# MCU025B_AltRouting_Misc.net
KiCad netlist of a schematic drawn in Altium Designer
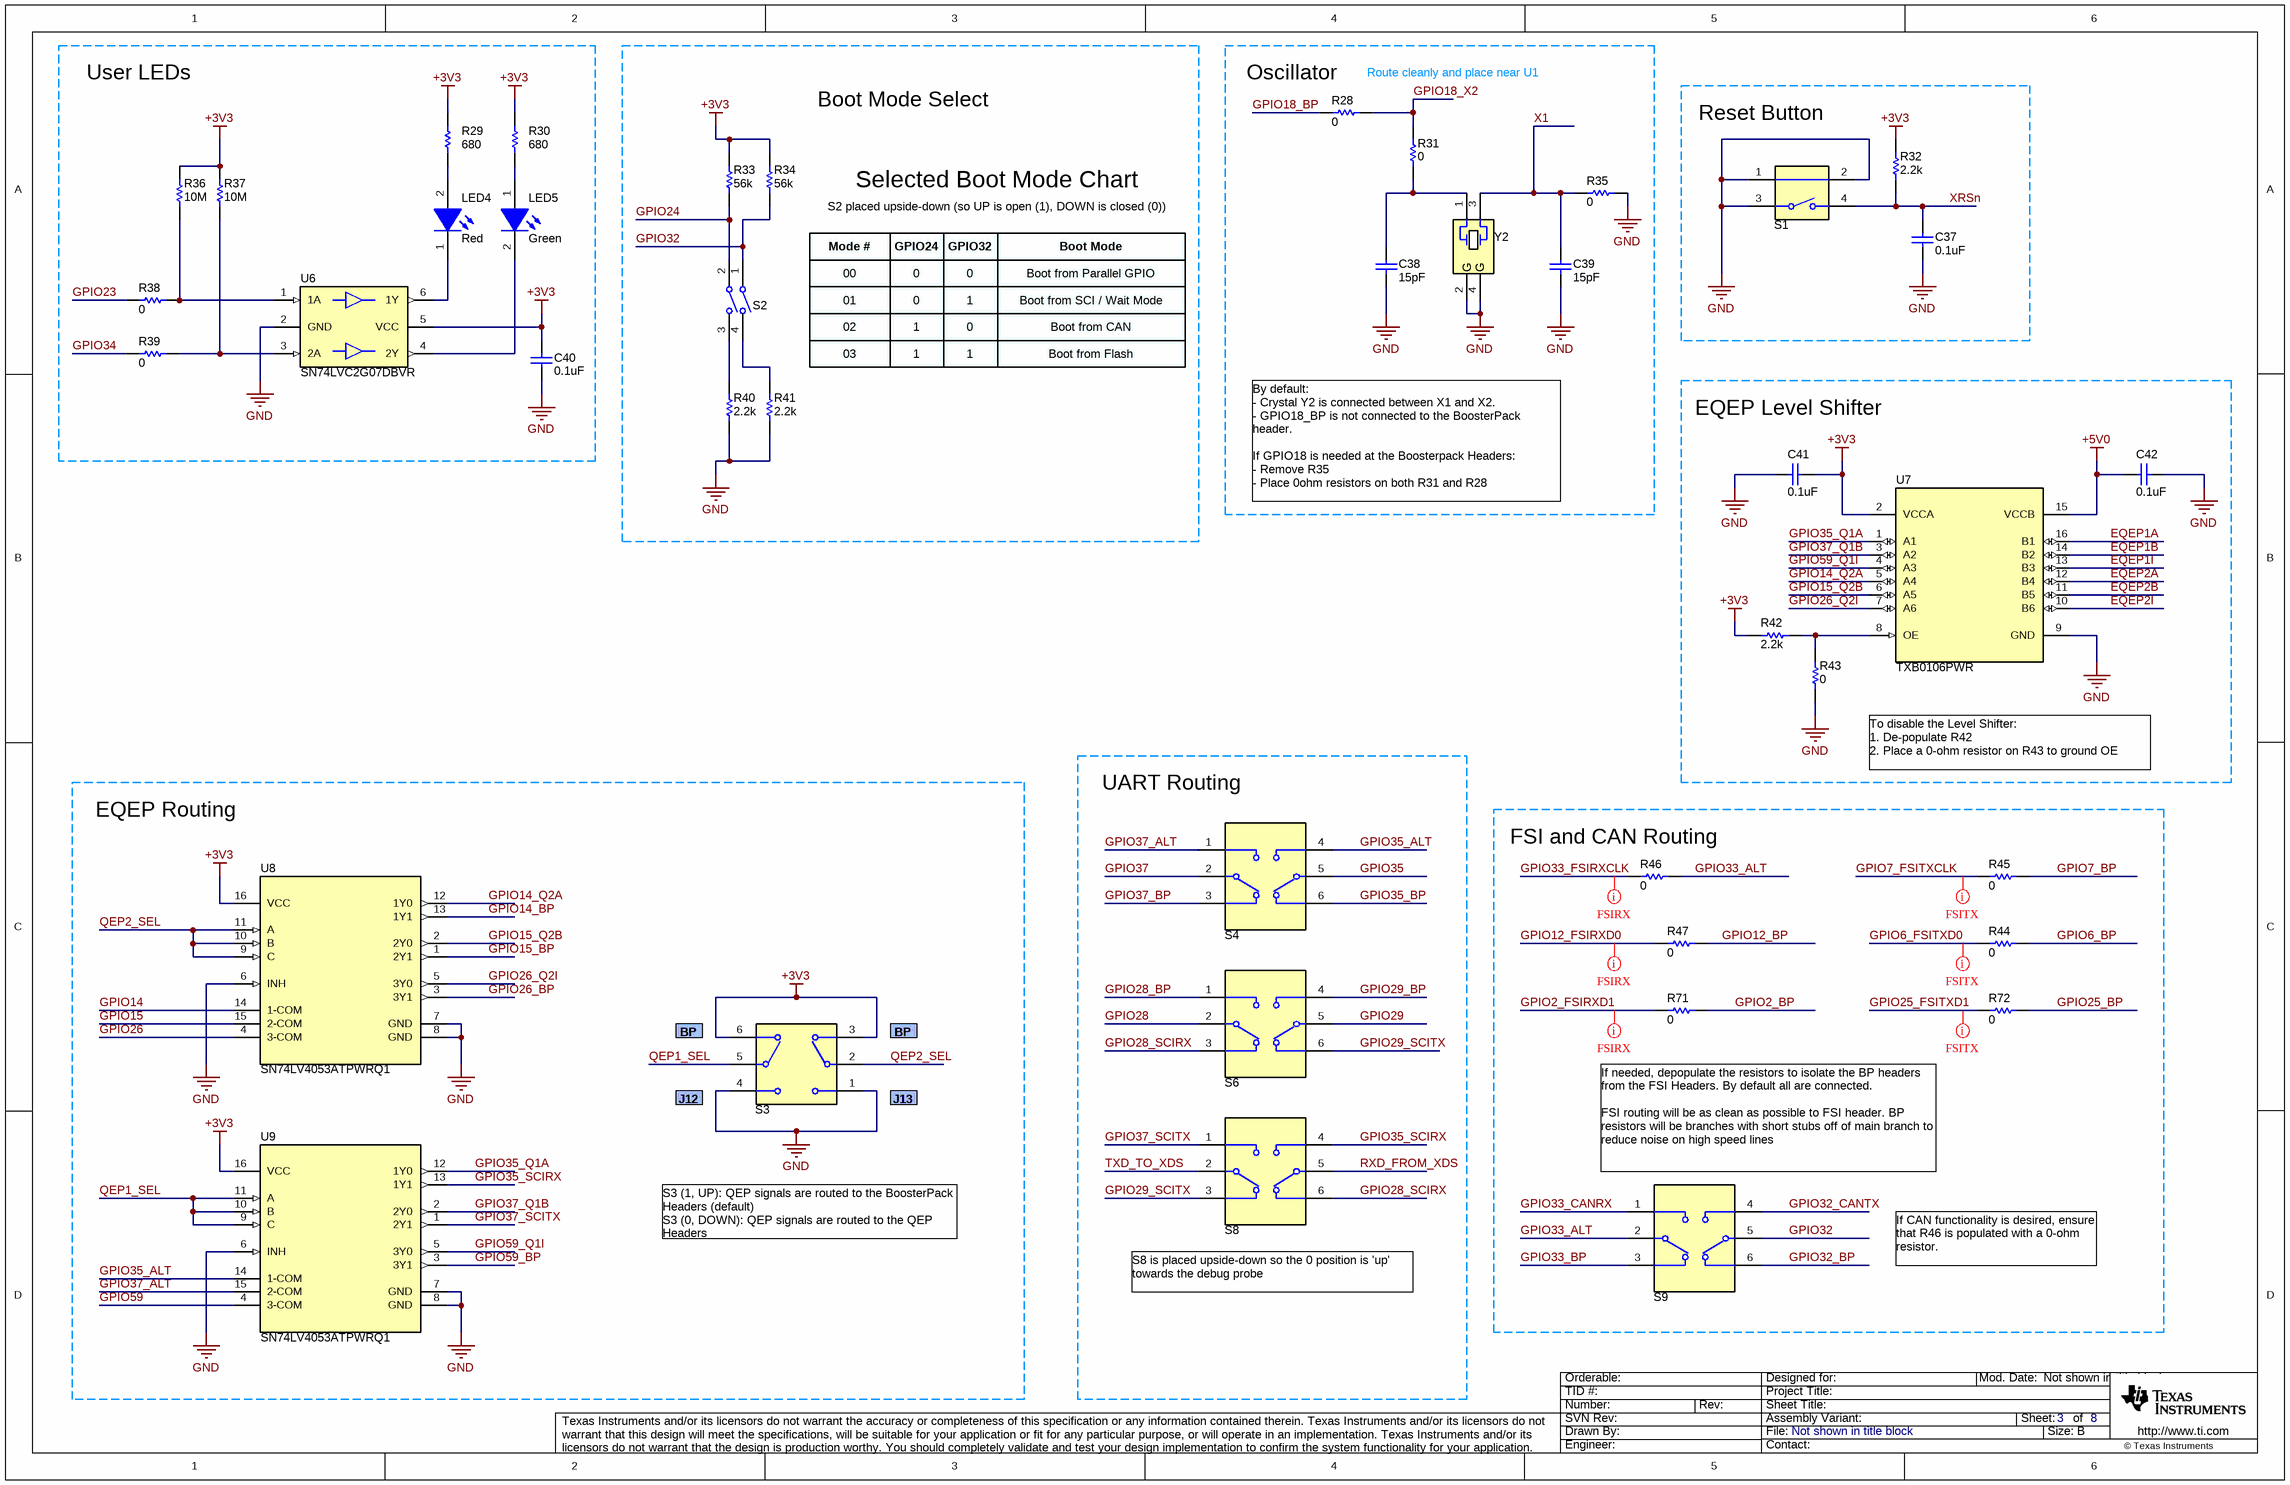
[diagram p0: MCU025B_AltRouting_Misc.SchDoc]

(export (version "E")
  (design (tool "Eeschema 10.0.6"))
  (components
    (comp (ref "C37")
      (value "GRM155R71A104KA01D")
      (footprint "0402")
      (description "CAP, CERM, 0.1 uF, 10 V, +/- 10%, X7R, 0402")
      (fields
        (field (name "VALUEDISPLAYED") "0.1uF")
        (field (name "MANUFACTURER") "MuRata")
        (field (name "PUBLISHER") "Texas Instruments")
      )
      (libsource (lib "Altium Vault - TI") (part "Capacitor"))
    )
    (comp (ref "C38")
      (value "GRM1555C1H150JA01D")
      (footprint "0402")
      (description "CAP, CERM, 15 pF, 50 V, +/- 5%, C0G/NP0, 0402")
      (fields
        (field (name "VALUEDISPLAYED") "15pF")
        (field (name "MANUFACTURER") "MuRata")
        (field (name "PUBLISHER") "Texas Instruments")
      )
      (libsource (lib "Altium Vault - TI") (part "Capacitor"))
    )
    (comp (ref "C39")
      (value "GRM1555C1H150JA01D")
      (footprint "0402")
      (description "CAP, CERM, 15 pF, 50 V, +/- 5%, C0G/NP0, 0402")
      (fields
        (field (name "VALUEDISPLAYED") "15pF")
        (field (name "MANUFACTURER") "MuRata")
        (field (name "PUBLISHER") "Texas Instruments")
      )
      (libsource (lib "Altium Vault - TI") (part "Capacitor"))
    )
    (comp (ref "C40")
      (value "GRM155R71A104KA01D")
      (footprint "0402")
      (description "CAP, CERM, 0.1 uF, 10 V, +/- 10%, X7R, 0402")
      (fields
        (field (name "VALUEDISPLAYED") "0.1uF")
        (field (name "MANUFACTURER") "MuRata")
        (field (name "PUBLISHER") "Texas Instruments")
      )
      (libsource (lib "Altium Vault - TI") (part "Capacitor"))
    )
    (comp (ref "C41")
      (value "GRM155R71A104KA01D")
      (footprint "0402")
      (description "CAP, CERM, 0.1 uF, 10 V, +/- 10%, X7R, 0402")
      (fields
        (field (name "VALUEDISPLAYED") "0.1uF")
        (field (name "MANUFACTURER") "MuRata")
        (field (name "PUBLISHER") "Texas Instruments")
      )
      (libsource (lib "Altium Vault - TI") (part "Capacitor"))
    )
    (comp (ref "C42")
      (value "GRM155R71A104KA01D")
      (footprint "0402")
      (description "CAP, CERM, 0.1 uF, 10 V, +/- 10%, X7R, 0402")
      (fields
        (field (name "VALUEDISPLAYED") "0.1uF")
        (field (name "MANUFACTURER") "MuRata")
        (field (name "PUBLISHER") "Texas Instruments")
      )
      (libsource (lib "Altium Vault - TI") (part "Capacitor"))
    )
    (comp (ref "LED4")
      (value "Red")
      (footprint "WL-SMCW_RED_0805")
      (description "LED, Red, SMD")
      (fields
        (field (name "MANUFACTURER") "Wurth Elektronik")
        (field (name "PARTNUMBER") "150080SS75000")
        (field (name "PUBLISHER") "Texas Instruments")
      )
      (libsource (lib "Altium Vault - TI") (part "LED_A2_K1"))
    )
    (comp (ref "LED5")
      (value "Green")
      (footprint "LED_LTST-C171")
      (description "LED, Green, SMD")
      (fields
        (field (name "MANUFACTURER") "Lite-On")
        (field (name "PARTNUMBER") "LTST-C171GKT")
        (field (name "PUBLISHER") "Texas Instruments")
      )
      (libsource (lib "Altium Vault - TI") (part "LED"))
    )
    (comp (ref "R28")
      (value "CRCW06030000Z0EA")
      (footprint "0603")
      (description "RES, 0, 5%, 0.1 W, AEC-Q200 Grade 0, 0603")
      (fields (field (name "VALUEDISPLAYED") "0") (field (name "MANUFACTURER") "Vishay-Dale"))
      (libsource (lib "Altium Vault - TI") (part "Resistor"))
    )
    (comp (ref "R29")
      (value "CRCW0402680RJNED")
      (footprint "0402")
      (description "RES, 680, 5%, 0.063 W, AEC-Q200 Grade 0, 0402")
      (fields (field (name "MANUFACTURER") "Vishay-Dale") (field (name "VALUEDISPLAYED") "680"))
      (libsource (lib "Altium Vault - TI") (part "CMP-0026962-3"))
    )
    (comp (ref "R30")
      (value "CRCW0402680RJNED")
      (footprint "0402")
      (description "RES, 680, 5%, 0.063 W, AEC-Q200 Grade 0, 0402")
      (fields (field (name "MANUFACTURER") "Vishay-Dale") (field (name "VALUEDISPLAYED") "680"))
      (libsource (lib "Altium Vault - TI") (part "CMP-0026962-3"))
    )
    (comp (ref "R31")
      (value "CRCW06030000Z0EA")
      (footprint "0603")
      (description "RES, 0, 5%, 0.1 W, AEC-Q200 Grade 0, 0603")
      (fields (field (name "VALUEDISPLAYED") "0") (field (name "MANUFACTURER") "Vishay-Dale"))
      (libsource (lib "Altium Vault - TI") (part "Resistor"))
    )
    (comp (ref "R32")
      (value "CRCW04022K20JNED")
      (footprint "0402")
      (description "RES, 2.2 k, 5%, 0.063 W, AEC-Q200 Grade 0, 0402")
      (fields (field (name "VALUEDISPLAYED") "2.2k") (field (name "MANUFACTURER") "Vishay-Dale"))
      (libsource (lib "Altium Vault - TI") (part "Resistor"))
    )
    (comp (ref "R33")
      (value "CRCW040256K0JNED")
      (footprint "0402")
      (description "RES, 56 k, 5%, 0.063 W, AEC-Q200 Grade 0, 0402")
      (fields (field (name "VALUEDISPLAYED") "56k") (field (name "MANUFACTURER") "Vishay-Dale"))
      (libsource (lib "Altium Vault - TI") (part "Resistor"))
    )
    (comp (ref "R34")
      (value "CRCW040256K0JNED")
      (footprint "0402")
      (description "RES, 56 k, 5%, 0.063 W, AEC-Q200 Grade 0, 0402")
      (fields (field (name "VALUEDISPLAYED") "56k") (field (name "MANUFACTURER") "Vishay-Dale"))
      (libsource (lib "Altium Vault - TI") (part "Resistor"))
    )
    (comp (ref "R35")
      (value "CRCW06030000Z0EA")
      (footprint "0603")
      (description "RES, 0, 5%, 0.1 W, AEC-Q200 Grade 0, 0603")
      (fields (field (name "VALUEDISPLAYED") "0") (field (name "MANUFACTURER") "Vishay-Dale"))
      (libsource (lib "Altium Vault - TI") (part "Resistor"))
    )
    (comp (ref "R36")
      (value "CRCW040210M0JNED")
      (footprint "0402")
      (description "RES, 10 M, 5%, 0.063 W, AEC-Q200 Grade 0, 0402")
      (fields (field (name "VALUEDISPLAYED") "10M") (field (name "MANUFACTURER") "Vishay-Dale"))
      (libsource (lib "Altium Vault - TI") (part "Resistor"))
    )
    (comp (ref "R37")
      (value "CRCW040210M0JNED")
      (footprint "0402")
      (description "RES, 10 M, 5%, 0.063 W, AEC-Q200 Grade 0, 0402")
      (fields (field (name "VALUEDISPLAYED") "10M") (field (name "MANUFACTURER") "Vishay-Dale"))
      (libsource (lib "Altium Vault - TI") (part "Resistor"))
    )
    (comp (ref "R38")
      (value "CRCW06030000Z0EA")
      (footprint "0603")
      (description "RES, 0, 5%, 0.1 W, AEC-Q200 Grade 0, 0603")
      (fields (field (name "VALUEDISPLAYED") "0") (field (name "MANUFACTURER") "Vishay-Dale"))
      (libsource (lib "Altium Vault - TI") (part "Resistor"))
    )
    (comp (ref "R39")
      (value "CRCW06030000Z0EA")
      (footprint "0603")
      (description "RES, 0, 5%, 0.1 W, AEC-Q200 Grade 0, 0603")
      (fields (field (name "VALUEDISPLAYED") "0") (field (name "MANUFACTURER") "Vishay-Dale"))
      (libsource (lib "Altium Vault - TI") (part "Resistor"))
    )
    (comp (ref "R40")
      (value "CRCW04022K20JNED")
      (footprint "0402")
      (description "RES, 2.2 k, 5%, 0.063 W, AEC-Q200 Grade 0, 0402")
      (fields (field (name "VALUEDISPLAYED") "2.2k") (field (name "MANUFACTURER") "Vishay-Dale"))
      (libsource (lib "Altium Vault - TI") (part "Resistor"))
    )
    (comp (ref "R41")
      (value "CRCW04022K20JNED")
      (footprint "0402")
      (description "RES, 2.2 k, 5%, 0.063 W, AEC-Q200 Grade 0, 0402")
      (fields (field (name "VALUEDISPLAYED") "2.2k") (field (name "MANUFACTURER") "Vishay-Dale"))
      (libsource (lib "Altium Vault - TI") (part "Resistor"))
    )
    (comp (ref "R42")
      (value "CRCW06032K20JNEA")
      (footprint "0603")
      (description "RES, 2.2 k, 5%, 0.1 W, AEC-Q200 Grade 0, 0603")
      (fields (field (name "VALUEDISPLAYED") "2.2k") (field (name "MANUFACTURER") "Vishay-Dale"))
      (libsource (lib "Altium Vault - TI") (part "Resistor"))
    )
    (comp (ref "R43")
      (value "CRCW06030000Z0EA")
      (footprint "0603")
      (description "RES, 0, 5%, 0.1 W, AEC-Q200 Grade 0, 0603")
      (fields (field (name "VALUEDISPLAYED") "0") (field (name "MANUFACTURER") "Vishay-Dale"))
      (libsource (lib "Altium Vault - TI") (part "Resistor"))
    )
    (comp (ref "R44")
      (value "CRCW06030000Z0EA")
      (footprint "0603")
      (description "RES, 0, 5%, 0.1 W, AEC-Q200 Grade 0, 0603")
      (fields (field (name "VALUEDISPLAYED") "0") (field (name "MANUFACTURER") "Vishay-Dale"))
      (libsource (lib "Altium Vault - TI") (part "Resistor"))
    )
    (comp (ref "R45")
      (value "CRCW06030000Z0EA")
      (footprint "0603")
      (description "RES, 0, 5%, 0.1 W, AEC-Q200 Grade 0, 0603")
      (fields (field (name "VALUEDISPLAYED") "0") (field (name "MANUFACTURER") "Vishay-Dale"))
      (libsource (lib "Altium Vault - TI") (part "Resistor"))
    )
    (comp (ref "R46")
      (value "CRCW06030000Z0EA")
      (footprint "0603")
      (description "RES, 0, 5%, 0.1 W, AEC-Q200 Grade 0, 0603")
      (fields (field (name "VALUEDISPLAYED") "0") (field (name "MANUFACTURER") "Vishay-Dale"))
      (libsource (lib "Altium Vault - TI") (part "Resistor"))
    )
    (comp (ref "R47")
      (value "CRCW06030000Z0EA")
      (footprint "0603")
      (description "RES, 0, 5%, 0.1 W, AEC-Q200 Grade 0, 0603")
      (fields (field (name "VALUEDISPLAYED") "0") (field (name "MANUFACTURER") "Vishay-Dale"))
      (libsource (lib "Altium Vault - TI") (part "Resistor"))
    )
    (comp (ref "R71")
      (value "CRCW06030000Z0EA")
      (footprint "0603")
      (description "RES, 0, 5%, 0.1 W, AEC-Q200 Grade 0, 0603")
      (fields (field (name "VALUEDISPLAYED") "0") (field (name "MANUFACTURER") "Vishay-Dale"))
      (libsource (lib "Altium Vault - TI") (part "Resistor"))
    )
    (comp (ref "R72")
      (value "CRCW06030000Z0EA")
      (footprint "0603")
      (description "RES, 0, 5%, 0.1 W, AEC-Q200 Grade 0, 0603")
      (fields (field (name "VALUEDISPLAYED") "0") (field (name "MANUFACTURER") "Vishay-Dale"))
      (libsource (lib "Altium Vault - TI") (part "Resistor"))
    )
    (comp (ref "S1")
      (value "1188E-1K2-V-TR")
      (footprint "SW_1188E")
      (description "Switch, SPST, 0.05 A, 12 VDC, SMD")
      (fields (field (name "MANUFACTURER") "Diptronics") (field (name "PUBLISHER") "Texas Instruments"))
      (libsource (lib "Altium Vault - TI") (part "SW_1188E"))
    )
    (comp (ref "S2")
      (value "218-2LPST")
      (footprint "SW_218-2LP")
      (description "Switch, SPST, 2 Pos, 25mA, 24VDC, SMD")
      (fields
        (field (name "MANUFACTURER") "CTS Electrocomponents")
        (field (name "PUBLISHER") "Texas Instruments")
      )
      (libsource (lib "Altium Vault - TI") (part "SW_2SPST"))
    )
    (comp (ref "S3")
      (value "CAS-D20TA")
      (footprint "SW_CAS-D20TA")
      (description "Switch, Dual SPDT,  2 Pos, 0.1A, 6VDC, SMD")
      (fields
        (field (name "MANUFACTURER") "Copal Electronics")
        (field (name "PUBLISHER") "Texas Instruments")
      )
      (libsource (lib "Altium Vault - TI") (part "SW_SPDT_CAS-D20TA"))
    )
    (comp (ref "S4")
      (value "CAS-220TA")
      (footprint "SW_CAS-220TA")
      (description "SLIDE SWITCH DPDT  .1A, SMT")
      (fields
        (field (name "MANUFACTURER") "Copal Electronics")
        (field (name "PUBLISHER") "Texas Instruments")
      )
      (libsource (lib "Altium Vault - TI") (part "SW_CAS-220TA"))
    )
    (comp (ref "S6")
      (value "CAS-220TA")
      (footprint "SW_CAS-220TA")
      (description "SLIDE SWITCH DPDT  .1A, SMT")
      (fields
        (field (name "MANUFACTURER") "Copal Electronics")
        (field (name "PUBLISHER") "Texas Instruments")
      )
      (libsource (lib "Altium Vault - TI") (part "SW_CAS-220TA"))
    )
    (comp (ref "S8")
      (value "CAS-220TA")
      (footprint "SW_CAS-220TA")
      (description "SLIDE SWITCH DPDT  .1A, SMT")
      (fields
        (field (name "MANUFACTURER") "Copal Electronics")
        (field (name "PUBLISHER") "Texas Instruments")
      )
      (libsource (lib "Altium Vault - TI") (part "SW_CAS-220TA"))
    )
    (comp (ref "S9")
      (value "CAS-220TA")
      (footprint "SW_CAS-220TA")
      (description "SLIDE SWITCH DPDT  .1A, SMT")
      (fields
        (field (name "MANUFACTURER") "Copal Electronics")
        (field (name "PUBLISHER") "Texas Instruments")
      )
      (libsource (lib "Altium Vault - TI") (part "SW_CAS-220TA"))
    )
    (comp (ref "U6")
      (value "SN74LVC2G07DBVR")
      (footprint "DBV0006A_N")
      (description "Dual Buffer/Driver with Open-Drain Output, DBV0006A, LARGE T&R")
      (fields
        (field (name "GENERIC PART NUMBER") "SN74LVC2G07")
        (field (name "MANUFACTURER") "Texas Instruments")
      )
      (libsource (lib "Altium Vault - TI") (part "CMP-0051789-2"))
    )
    (comp (ref "U7")
      (value "TXB0106PWR")
      (footprint "PW0016A_N")
      (fields
        (field (name "MANUFACTURER") "Texas Instruments")
        (field (name "PUBLISHER") "Texas Instruments")
      )
      (libsource (lib "Altium Vault - TI") (part "TXB0106PW"))
    )
    (comp (ref "U8")
      (value "SN74LV4053ATPWRQ1")
      (footprint "PW0016A_L")
      (description "TRIPLE 2-CHANNEL ANALOG MULTIPLEXER/DEMULTIPLEXER, PW0016A (TSSOP-16)")
      (fields
        (field (name "PARTNUMBER") "SN74LV4053ATPWRQ1")
        (field (name "MANUFACTURER") "Texas Instruments")
        (field (name "PUBLISHER") "Texas Instruments")
      )
      (libsource (lib "Altium Vault - TI") (part "SN74LV4053A-Q1"))
    )
    (comp (ref "U9")
      (value "SN74LV4053ATPWRQ1")
      (footprint "PW0016A_L")
      (description "TRIPLE 2-CHANNEL ANALOG MULTIPLEXER/DEMULTIPLEXER, PW0016A (TSSOP-16)")
      (fields
        (field (name "PARTNUMBER") "SN74LV4053ATPWRQ1")
        (field (name "MANUFACTURER") "Texas Instruments")
        (field (name "PUBLISHER") "Texas Instruments")
      )
      (libsource (lib "Altium Vault - TI") (part "SN74LV4053A-Q1"))
    )
    (comp (ref "Y2")
      (value "ECS-200-18-30B-AGN-TR")
      (footprint "ECS_ECX-53B")
      (description "Crystal, 20 MHz, 25 ppm, 18, SMD")
      (fields (field (name "MANUFACTURER") "ECS Inc."))
      (libsource (lib "Altium Vault - TI") (part "CMP-0080365-1"))
    )
  )
  (nets
    (net (code "1") (name "+3V3") (class "Default")
      (node (ref "C40") (pin "2") (pinfunction "2_2") (pintype "passive"))
      (node (ref "C41") (pin "1") (pinfunction "1_1") (pintype "passive"))
      (node (ref "R29") (pin "2") (pinfunction "2_2") (pintype "passive"))
      (node (ref "R30") (pin "2") (pinfunction "2_2") (pintype "passive"))
      (node (ref "R32") (pin "2") (pinfunction "2_2") (pintype "passive"))
      (node (ref "R33") (pin "2") (pinfunction "2_2") (pintype "passive"))
      (node (ref "R34") (pin "2") (pinfunction "2_2") (pintype "passive"))
      (node (ref "R36") (pin "2") (pinfunction "2_2") (pintype "passive"))
      (node (ref "R37") (pin "2") (pinfunction "2_2") (pintype "passive"))
      (node (ref "R42") (pin "1") (pinfunction "1_1") (pintype "passive"))
      (node (ref "S3") (pin "3") (pinfunction "3_3") (pintype "passive"))
      (node (ref "S3") (pin "6") (pinfunction "6_6") (pintype "passive"))
      (node (ref "U6") (pin "5") (pinfunction "VCC_5") (pintype "power_in"))
      (node (ref "U7") (pin "2") (pinfunction "VCCA_2") (pintype "power_in"))
      (node (ref "U8") (pin "16") (pinfunction "VCC_16") (pintype "power_in"))
      (node (ref "U9") (pin "16") (pinfunction "VCC_16") (pintype "power_in"))
    )
    (net (code "2") (name "+5V0") (class "Default")
      (node (ref "C42") (pin "2") (pinfunction "2_2") (pintype "passive"))
      (node (ref "U7") (pin "15") (pinfunction "VCCB_15") (pintype "power_in"))
    )
    (net (code "3") (name "/EQEP1A") (class "Default")
      (node (ref "U7") (pin "16") (pinfunction "B1_16") (pintype "bidirectional"))
    )
    (net (code "4") (name "/EQEP1B") (class "Default")
      (node (ref "U7") (pin "14") (pinfunction "B2_14") (pintype "bidirectional"))
    )
    (net (code "5") (name "/EQEP1I") (class "Default")
      (node (ref "U7") (pin "13") (pinfunction "B3_13") (pintype "bidirectional"))
    )
    (net (code "6") (name "/EQEP2A") (class "Default")
      (node (ref "U7") (pin "12") (pinfunction "B4_12") (pintype "bidirectional"))
    )
    (net (code "7") (name "/EQEP2B") (class "Default")
      (node (ref "U7") (pin "11") (pinfunction "B5_11") (pintype "bidirectional"))
    )
    (net (code "8") (name "/EQEP2I") (class "Default")
      (node (ref "U7") (pin "10") (pinfunction "B6_10") (pintype "bidirectional"))
    )
    (net (code "9") (name "/GPIO2_BP") (class "Default")
      (node (ref "R71") (pin "2") (pinfunction "2_2") (pintype "passive"))
    )
    (net (code "10") (name "/GPIO2_FSIRXD1") (class "Default")
      (node (ref "R71") (pin "1") (pinfunction "1_1") (pintype "passive"))
    )
    (net (code "11") (name "/GPIO6_BP") (class "Default")
      (node (ref "R44") (pin "2") (pinfunction "2_2") (pintype "passive"))
    )
    (net (code "12") (name "/GPIO6_FSITXD0") (class "Default")
      (node (ref "R44") (pin "1") (pinfunction "1_1") (pintype "passive"))
    )
    (net (code "13") (name "/GPIO7_BP") (class "Default")
      (node (ref "R45") (pin "2") (pinfunction "2_2") (pintype "passive"))
    )
    (net (code "14") (name "/GPIO7_FSITXCLK") (class "Default")
      (node (ref "R45") (pin "1") (pinfunction "1_1") (pintype "passive"))
    )
    (net (code "15") (name "/GPIO12_BP") (class "Default")
      (node (ref "R47") (pin "2") (pinfunction "2_2") (pintype "passive"))
    )
    (net (code "16") (name "/GPIO12_FSIRXD0") (class "Default")
      (node (ref "R47") (pin "1") (pinfunction "1_1") (pintype "passive"))
    )
    (net (code "17") (name "/GPIO14") (class "Default")
      (node (ref "U8") (pin "14") (pinfunction "1-COM_14") (pintype "passive"))
    )
    (net (code "18") (name "/GPIO14_BP") (class "Default")
      (node (ref "U8") (pin "13") (pinfunction "1Y1_13") (pintype "output"))
    )
    (net (code "19") (name "/GPIO14_Q2A") (class "Default")
      (node (ref "U7") (pin "5") (pinfunction "A4_5") (pintype "bidirectional"))
      (node (ref "U8") (pin "12") (pinfunction "1Y0_12") (pintype "output"))
    )
    (net (code "20") (name "/GPIO15") (class "Default")
      (node (ref "U8") (pin "15") (pinfunction "2-COM_15") (pintype "passive"))
    )
    (net (code "21") (name "/GPIO15_BP") (class "Default")
      (node (ref "U8") (pin "1") (pinfunction "2Y1_1") (pintype "output"))
    )
    (net (code "22") (name "/GPIO15_Q2B") (class "Default")
      (node (ref "U7") (pin "6") (pinfunction "A5_6") (pintype "bidirectional"))
      (node (ref "U8") (pin "2") (pinfunction "2Y0_2") (pintype "output"))
    )
    (net (code "23") (name "/GPIO18_BP") (class "Default")
      (node (ref "R28") (pin "1") (pinfunction "1_1") (pintype "passive"))
    )
    (net (code "24") (name "/GPIO18_X2") (class "Default")
      (node (ref "R28") (pin "2") (pinfunction "2_2") (pintype "passive"))
      (node (ref "R31") (pin "2") (pinfunction "2_2") (pintype "passive"))
    )
    (net (code "25") (name "/GPIO23") (class "Default")
      (node (ref "R38") (pin "1") (pinfunction "1_1") (pintype "passive"))
    )
    (net (code "26") (name "/GPIO24") (class "Default")
      (node (ref "R33") (pin "1") (pinfunction "1_1") (pintype "passive"))
      (node (ref "S2") (pin "2") (pinfunction "2_2") (pintype "passive"))
    )
    (net (code "27") (name "/GPIO25_BP") (class "Default")
      (node (ref "R72") (pin "2") (pinfunction "2_2") (pintype "passive"))
    )
    (net (code "28") (name "/GPIO25_FSITXD1") (class "Default")
      (node (ref "R72") (pin "1") (pinfunction "1_1") (pintype "passive"))
    )
    (net (code "29") (name "/GPIO26") (class "Default")
      (node (ref "U8") (pin "4") (pinfunction "3-COM_4") (pintype "passive"))
    )
    (net (code "30") (name "/GPIO26_BP") (class "Default")
      (node (ref "U8") (pin "3") (pinfunction "3Y1_3") (pintype "output"))
    )
    (net (code "31") (name "/GPIO26_Q2I") (class "Default")
      (node (ref "U7") (pin "7") (pinfunction "A6_7") (pintype "bidirectional"))
      (node (ref "U8") (pin "5") (pinfunction "3Y0_5") (pintype "output"))
    )
    (net (code "32") (name "/GPIO28") (class "Default")
      (node (ref "S6") (pin "2") (pinfunction "2_2") (pintype "passive"))
    )
    (net (code "33") (name "/GPIO28_BP") (class "Default")
      (node (ref "S6") (pin "1") (pinfunction "1_1") (pintype "passive"))
    )
    (net (code "34") (name "/GPIO28_SCIRX") (class "Default")
      (node (ref "S6") (pin "3") (pinfunction "3_3") (pintype "passive"))
      (node (ref "S8") (pin "6") (pinfunction "6_6") (pintype "passive"))
    )
    (net (code "35") (name "/GPIO29") (class "Default")
      (node (ref "S6") (pin "5") (pinfunction "5_5") (pintype "passive"))
    )
    (net (code "36") (name "/GPIO29_BP") (class "Default")
      (node (ref "S6") (pin "4") (pinfunction "4_4") (pintype "passive"))
    )
    (net (code "37") (name "/GPIO29_SCITX") (class "Default")
      (node (ref "S6") (pin "6") (pinfunction "6_6") (pintype "passive"))
      (node (ref "S8") (pin "3") (pinfunction "3_3") (pintype "passive"))
    )
    (net (code "38") (name "/GPIO32") (class "Default")
      (node (ref "R34") (pin "1") (pinfunction "1_1") (pintype "passive"))
      (node (ref "S2") (pin "1") (pinfunction "1_1") (pintype "passive"))
      (node (ref "S9") (pin "5") (pinfunction "5_5") (pintype "passive"))
    )
    (net (code "39") (name "/GPIO32_BP") (class "Default")
      (node (ref "S9") (pin "6") (pinfunction "6_6") (pintype "passive"))
    )
    (net (code "40") (name "/GPIO32_CANTX") (class "Default")
      (node (ref "S9") (pin "4") (pinfunction "4_4") (pintype "passive"))
    )
    (net (code "41") (name "/GPIO33_ALT") (class "Default")
      (node (ref "R46") (pin "2") (pinfunction "2_2") (pintype "passive"))
      (node (ref "S9") (pin "2") (pinfunction "2_2") (pintype "passive"))
    )
    (net (code "42") (name "/GPIO33_BP") (class "Default")
      (node (ref "S9") (pin "3") (pinfunction "3_3") (pintype "passive"))
    )
    (net (code "43") (name "/GPIO33_CANRX") (class "Default")
      (node (ref "S9") (pin "1") (pinfunction "1_1") (pintype "passive"))
    )
    (net (code "44") (name "/GPIO33_FSIRXCLK") (class "Default")
      (node (ref "R46") (pin "1") (pinfunction "1_1") (pintype "passive"))
    )
    (net (code "45") (name "/GPIO34") (class "Default")
      (node (ref "R39") (pin "1") (pinfunction "1_1") (pintype "passive"))
    )
    (net (code "46") (name "/GPIO35") (class "Default")
      (node (ref "S4") (pin "5") (pinfunction "5_5") (pintype "passive"))
    )
    (net (code "47") (name "/GPIO35_ALT") (class "Default")
      (node (ref "S4") (pin "4") (pinfunction "4_4") (pintype "passive"))
      (node (ref "U9") (pin "14") (pinfunction "1-COM_14") (pintype "passive"))
    )
    (net (code "48") (name "/GPIO35_BP") (class "Default")
      (node (ref "S4") (pin "6") (pinfunction "6_6") (pintype "passive"))
    )
    (net (code "49") (name "/GPIO35_Q1A") (class "Default")
      (node (ref "U7") (pin "1") (pinfunction "A1_1") (pintype "bidirectional"))
      (node (ref "U9") (pin "12") (pinfunction "1Y0_12") (pintype "output"))
    )
    (net (code "50") (name "/GPIO35_SCIRX") (class "Default")
      (node (ref "S8") (pin "4") (pinfunction "4_4") (pintype "passive"))
      (node (ref "U9") (pin "13") (pinfunction "1Y1_13") (pintype "output"))
    )
    (net (code "51") (name "/GPIO37") (class "Default")
      (node (ref "S4") (pin "2") (pinfunction "2_2") (pintype "passive"))
    )
    (net (code "52") (name "/GPIO37_ALT") (class "Default")
      (node (ref "S4") (pin "1") (pinfunction "1_1") (pintype "passive"))
      (node (ref "U9") (pin "15") (pinfunction "2-COM_15") (pintype "passive"))
    )
    (net (code "53") (name "/GPIO37_BP") (class "Default")
      (node (ref "S4") (pin "3") (pinfunction "3_3") (pintype "passive"))
    )
    (net (code "54") (name "/GPIO37_Q1B") (class "Default")
      (node (ref "U7") (pin "3") (pinfunction "A2_3") (pintype "bidirectional"))
      (node (ref "U9") (pin "2") (pinfunction "2Y0_2") (pintype "output"))
    )
    (net (code "55") (name "/GPIO37_SCITX") (class "Default")
      (node (ref "S8") (pin "1") (pinfunction "1_1") (pintype "passive"))
      (node (ref "U9") (pin "1") (pinfunction "2Y1_1") (pintype "output"))
    )
    (net (code "56") (name "/GPIO59") (class "Default")
      (node (ref "U9") (pin "4") (pinfunction "3-COM_4") (pintype "passive"))
    )
    (net (code "57") (name "/GPIO59_BP") (class "Default")
      (node (ref "U9") (pin "3") (pinfunction "3Y1_3") (pintype "output"))
    )
    (net (code "58") (name "/GPIO59_Q1I") (class "Default")
      (node (ref "U7") (pin "4") (pinfunction "A3_4") (pintype "bidirectional"))
      (node (ref "U9") (pin "5") (pinfunction "3Y0_5") (pintype "output"))
    )
    (net (code "59") (name "/QEP1_SEL") (class "Default")
      (node (ref "S3") (pin "5") (pinfunction "C_5") (pintype "passive"))
      (node (ref "U9") (pin "10") (pinfunction "B_10") (pintype "input"))
      (node (ref "U9") (pin "11") (pinfunction "A_11") (pintype "input"))
      (node (ref "U9") (pin "9") (pinfunction "C_9") (pintype "input"))
    )
    (net (code "60") (name "/QEP2_SEL") (class "Default")
      (node (ref "S3") (pin "2") (pinfunction "C_2") (pintype "passive"))
      (node (ref "U8") (pin "10") (pinfunction "B_10") (pintype "input"))
      (node (ref "U8") (pin "11") (pinfunction "A_11") (pintype "input"))
      (node (ref "U8") (pin "9") (pinfunction "C_9") (pintype "input"))
    )
    (net (code "61") (name "/RXD_FROM_XDS") (class "Default")
      (node (ref "S8") (pin "5") (pinfunction "5_5") (pintype "passive"))
    )
    (net (code "62") (name "/TXD_TO_XDS") (class "Default")
      (node (ref "S8") (pin "2") (pinfunction "2_2") (pintype "passive"))
    )
    (net (code "63") (name "/X1") (class "Default")
      (node (ref "C39") (pin "1") (pinfunction "1_1") (pintype "passive"))
      (node (ref "R35") (pin "1") (pinfunction "1_1") (pintype "passive"))
      (node (ref "Y2") (pin "3") (pinfunction "3_3") (pintype "passive"))
    )
    (net (code "64") (name "/XRSn") (class "Default")
      (node (ref "C37") (pin "2") (pinfunction "2_2") (pintype "passive"))
      (node (ref "R32") (pin "1") (pinfunction "1_1") (pintype "passive"))
      (node (ref "S1") (pin "4") (pinfunction "4_4") (pintype "passive"))
    )
    (net (code "65") (name "GND") (class "Default")
      (node (ref "C37") (pin "1") (pinfunction "1_1") (pintype "passive"))
      (node (ref "C38") (pin "2") (pinfunction "2_2") (pintype "passive"))
      (node (ref "C39") (pin "2") (pinfunction "2_2") (pintype "passive"))
      (node (ref "C40") (pin "1") (pinfunction "1_1") (pintype "passive"))
      (node (ref "C41") (pin "2") (pinfunction "2_2") (pintype "passive"))
      (node (ref "C42") (pin "1") (pinfunction "1_1") (pintype "passive"))
      (node (ref "R35") (pin "2") (pinfunction "2_2") (pintype "passive"))
      (node (ref "R40") (pin "1") (pinfunction "1_1") (pintype "passive"))
      (node (ref "R41") (pin "1") (pinfunction "1_1") (pintype "passive"))
      (node (ref "R43") (pin "1") (pinfunction "1_1") (pintype "passive"))
      (node (ref "S1") (pin "1") (pinfunction "1_1") (pintype "passive"))
      (node (ref "S1") (pin "2") (pinfunction "2_2") (pintype "passive"))
      (node (ref "S1") (pin "3") (pinfunction "3_3") (pintype "passive"))
      (node (ref "S3") (pin "1") (pinfunction "1_1") (pintype "passive"))
      (node (ref "S3") (pin "4") (pinfunction "4_4") (pintype "passive"))
      (node (ref "U6") (pin "2") (pinfunction "GND_2") (pintype "power_in"))
      (node (ref "U7") (pin "9") (pinfunction "GND_9") (pintype "power_in"))
      (node (ref "U8") (pin "6") (pinfunction "INH_6") (pintype "input"))
      (node (ref "U8") (pin "7") (pinfunction "GND_7") (pintype "power_in"))
      (node (ref "U8") (pin "8") (pinfunction "GND_8") (pintype "power_in"))
      (node (ref "U9") (pin "6") (pinfunction "INH_6") (pintype "input"))
      (node (ref "U9") (pin "7") (pinfunction "GND_7") (pintype "power_in"))
      (node (ref "U9") (pin "8") (pinfunction "GND_8") (pintype "power_in"))
      (node (ref "Y2") (pin "2") (pinfunction "GND_2") (pintype "power_in"))
      (node (ref "Y2") (pin "4") (pinfunction "GND_4") (pintype "power_in"))
    )
    (net (code "66") (name "Net-(C38-Pad1)") (class "Default")
      (node (ref "C38") (pin "1") (pinfunction "1_1") (pintype "passive"))
      (node (ref "R31") (pin "1") (pinfunction "1_1") (pintype "passive"))
      (node (ref "Y2") (pin "1") (pinfunction "1_1") (pintype "passive"))
    )
    (net (code "67") (name "Net-(LED4-A)") (class "Default")
      (node (ref "LED4") (pin "2") (pinfunction "A_2") (pintype "passive"))
      (node (ref "R29") (pin "1") (pinfunction "1_1") (pintype "passive"))
    )
    (net (code "68") (name "Net-(LED4-K)") (class "Default")
      (node (ref "LED4") (pin "1") (pinfunction "K_1") (pintype "passive"))
      (node (ref "U6") (pin "6") (pinfunction "1Y_6") (pintype "output"))
    )
    (net (code "69") (name "Net-(LED5-A)") (class "Default")
      (node (ref "LED5") (pin "1") (pinfunction "A_1") (pintype "passive"))
      (node (ref "R30") (pin "1") (pinfunction "1_1") (pintype "passive"))
    )
    (net (code "70") (name "Net-(LED5-K)") (class "Default")
      (node (ref "LED5") (pin "2") (pinfunction "K_2") (pintype "passive"))
      (node (ref "U6") (pin "4") (pinfunction "2Y_4") (pintype "output"))
    )
    (net (code "71") (name "Net-(R40-Pad2)") (class "Default")
      (node (ref "R40") (pin "2") (pinfunction "2_2") (pintype "passive"))
      (node (ref "S2") (pin "3") (pinfunction "3_3") (pintype "passive"))
    )
    (net (code "72") (name "Net-(R41-Pad2)") (class "Default")
      (node (ref "R41") (pin "2") (pinfunction "2_2") (pintype "passive"))
      (node (ref "S2") (pin "4") (pinfunction "4_4") (pintype "passive"))
    )
    (net (code "73") (name "Net-(U6-1A)") (class "Default")
      (node (ref "R36") (pin "1") (pinfunction "1_1") (pintype "passive"))
      (node (ref "R38") (pin "2") (pinfunction "2_2") (pintype "passive"))
      (node (ref "U6") (pin "1") (pinfunction "1A_1") (pintype "input"))
    )
    (net (code "74") (name "Net-(U6-2A)") (class "Default")
      (node (ref "R37") (pin "1") (pinfunction "1_1") (pintype "passive"))
      (node (ref "R39") (pin "2") (pinfunction "2_2") (pintype "passive"))
      (node (ref "U6") (pin "3") (pinfunction "2A_3") (pintype "input"))
    )
    (net (code "75") (name "Net-(U7-OE)") (class "Default")
      (node (ref "R42") (pin "2") (pinfunction "2_2") (pintype "passive"))
      (node (ref "R43") (pin "2") (pinfunction "2_2") (pintype "passive"))
      (node (ref "U7") (pin "8") (pinfunction "OE_8") (pintype "input"))
    )
  )
)
